# Launch_Tower_Power_Interface_Board_v1-2.net
KiCad netlist of a schematic drawn in EAGLE
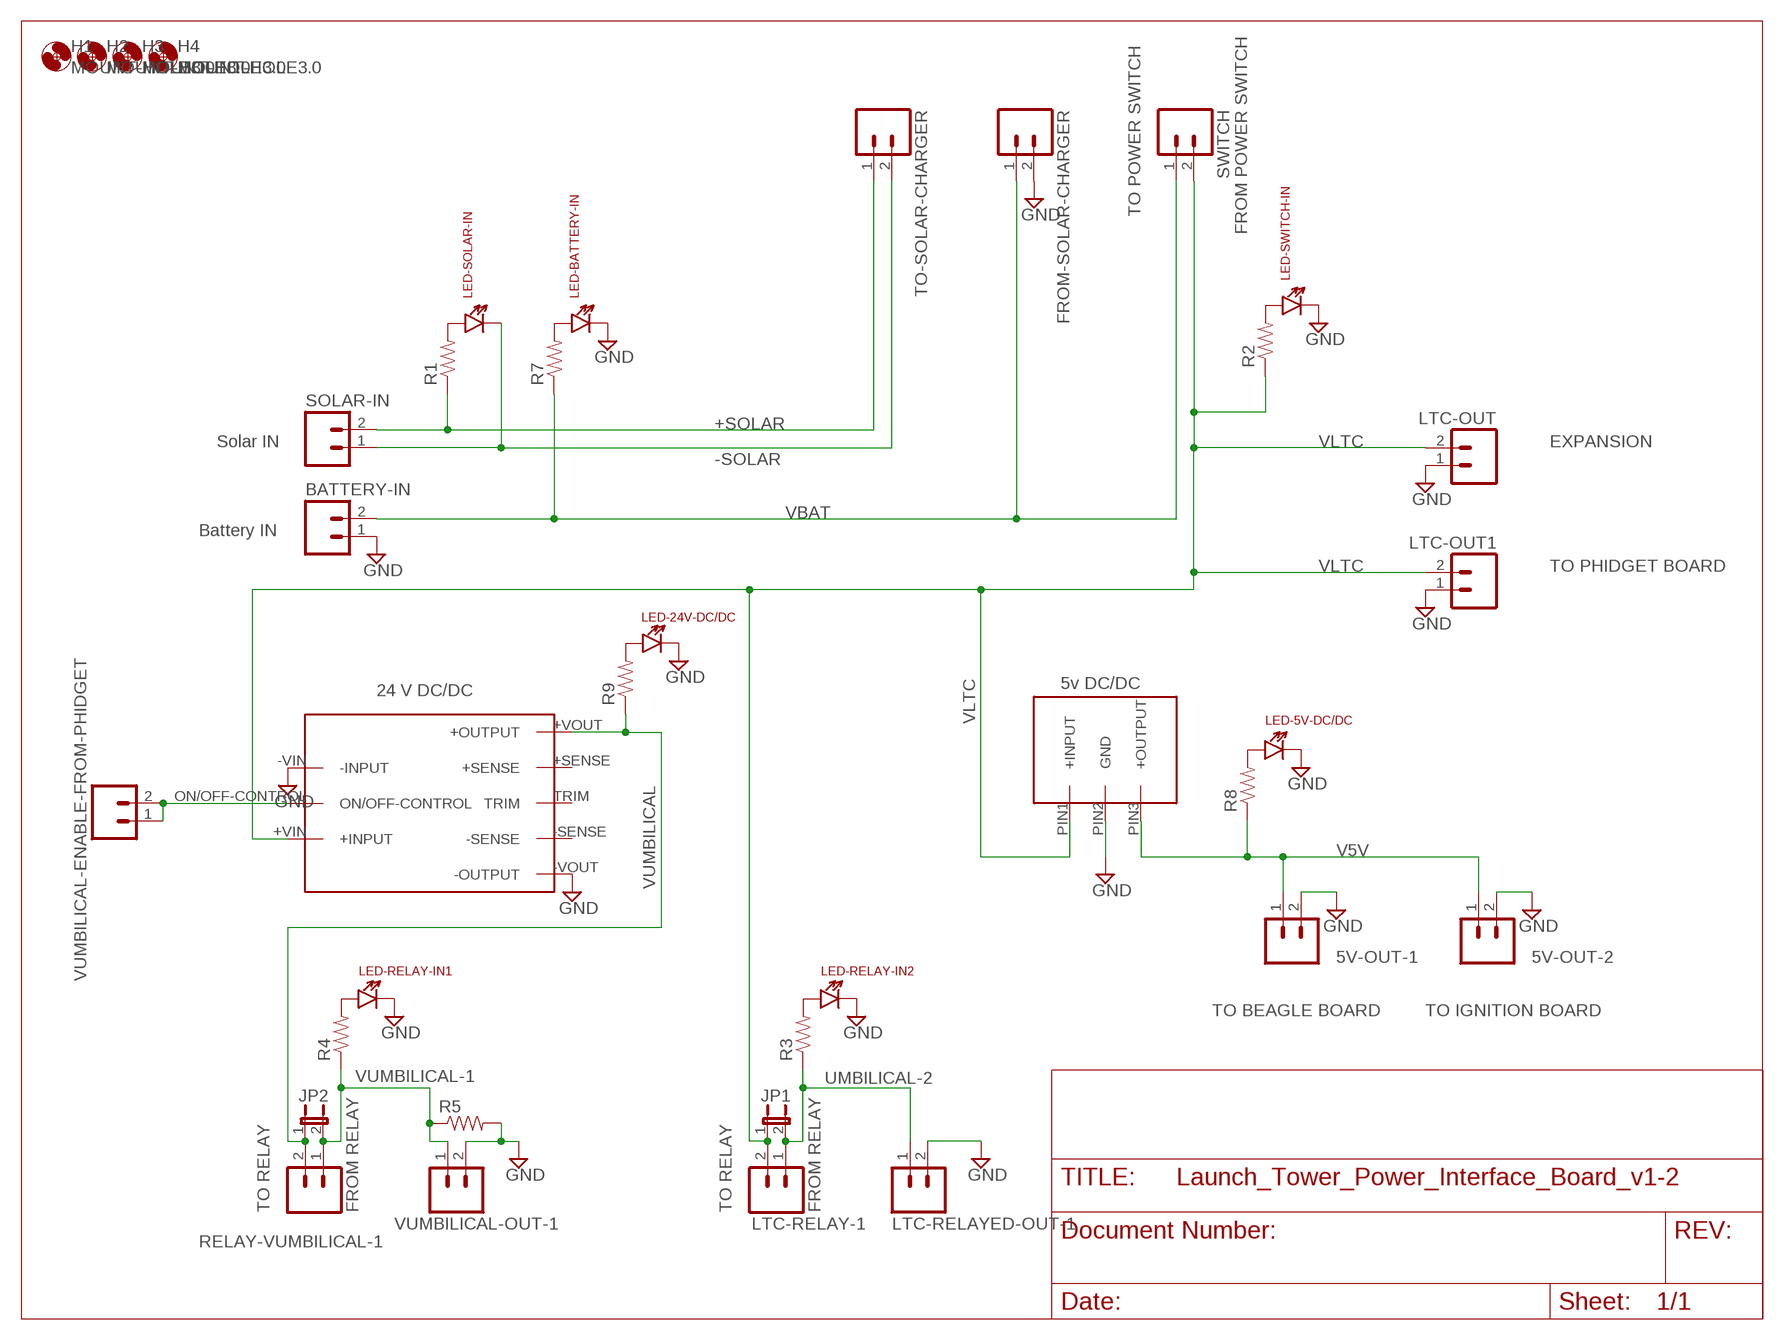
[diagram p0: schematic, sheet 1]

(export (version "E")
  (design (tool "Eeschema 10.0.6"))
  (components
    (comp (ref "5V-OUT-1")
      (value "M025MM")
      (footprint "eagle-import:SCREWTERMINAL-5MM-2")
      (libsource (lib "eagle-import") (part "M025MM"))
    )
    (comp (ref "5V-OUT-2")
      (value "M025MM")
      (footprint "eagle-import:SCREWTERMINAL-5MM-2")
      (libsource (lib "eagle-import") (part "M025MM"))
    )
    (comp (ref "BATTERY-IN")
      (value "M025MM")
      (footprint "eagle-import:SCREWTERMINAL-5MM-2")
      (libsource (lib "eagle-import") (part "M025MM"))
    )
    (comp (ref "FROM-SOLAR-CHARGER")
      (value "M025MM")
      (footprint "eagle-import:SCREWTERMINAL-5MM-2")
      (libsource (lib "eagle-import") (part "M025MM"))
    )
    (comp (ref "H1")
      (value "MOUNT-HOLE3.0")
      (footprint "eagle-import:3,0")
      (libsource (lib "eagle-import") (part "MOUNT-HOLE3.0"))
    )
    (comp (ref "H2")
      (value "MOUNT-HOLE3.0")
      (footprint "eagle-import:3,0")
      (libsource (lib "eagle-import") (part "MOUNT-HOLE3.0"))
    )
    (comp (ref "H3")
      (value "MOUNT-HOLE3.0")
      (footprint "eagle-import:3,0")
      (libsource (lib "eagle-import") (part "MOUNT-HOLE3.0"))
    )
    (comp (ref "H4")
      (value "MOUNT-HOLE3.0")
      (footprint "eagle-import:3,0")
      (libsource (lib "eagle-import") (part "MOUNT-HOLE3.0"))
    )
    (comp (ref "JP1")
      (value "JUMPER-2PTH")
      (footprint "eagle-import:1X02")
      (libsource (lib "eagle-import") (part "JUMPER-2PTH"))
    )
    (comp (ref "JP2")
      (value "JUMPER-2PTH")
      (footprint "eagle-import:1X02")
      (libsource (lib "eagle-import") (part "JUMPER-2PTH"))
    )
    (comp (ref "LED-5V-DC/DC")
      (value "LTE-302")
      (footprint "eagle-import:LTE-302")
      (libsource (lib "eagle-import") (part "LTE-302"))
    )
    (comp (ref "LED-24V-DC/DC")
      (value "LTE-302")
      (footprint "eagle-import:LTE-302")
      (libsource (lib "eagle-import") (part "LTE-302"))
    )
    (comp (ref "LED-BATTERY-IN")
      (value "LTE-302")
      (footprint "eagle-import:LTE-302")
      (libsource (lib "eagle-import") (part "LTE-302"))
    )
    (comp (ref "LED-RELAY-IN1")
      (value "LTE-302")
      (footprint "eagle-import:LTE-302")
      (libsource (lib "eagle-import") (part "LTE-302"))
    )
    (comp (ref "LED-RELAY-IN2")
      (value "LTE-302")
      (footprint "eagle-import:LTE-302")
      (libsource (lib "eagle-import") (part "LTE-302"))
    )
    (comp (ref "LED-SOLAR-IN")
      (value "LTE-302")
      (footprint "eagle-import:LTE-302")
      (libsource (lib "eagle-import") (part "LTE-302"))
    )
    (comp (ref "LED-SWITCH-IN")
      (value "LTE-302")
      (footprint "eagle-import:LTE-302")
      (libsource (lib "eagle-import") (part "LTE-302"))
    )
    (comp (ref "LTC-OUT")
      (value "M025MM")
      (footprint "eagle-import:SCREWTERMINAL-5MM-2")
      (libsource (lib "eagle-import") (part "M025MM"))
    )
    (comp (ref "LTC-OUT1")
      (value "M025MM")
      (footprint "eagle-import:SCREWTERMINAL-5MM-2")
      (libsource (lib "eagle-import") (part "M025MM"))
    )
    (comp (ref "LTC-RELAY-1")
      (value "M025MM")
      (footprint "eagle-import:SCREWTERMINAL-5MM-2")
      (libsource (lib "eagle-import") (part "M025MM"))
    )
    (comp (ref "LTC-RELAYED-OUT-1")
      (value "M025MM")
      (footprint "eagle-import:SCREWTERMINAL-5MM-2")
      (libsource (lib "eagle-import") (part "M025MM"))
    )
    (comp (ref "R1")
      (value "RESISTORPTH-1/2W")
      (footprint "eagle-import:AXIAL-0.5")
      (libsource (lib "eagle-import") (part "RESISTORPTH-1/2W"))
    )
    (comp (ref "R2")
      (value "RESISTORPTH-1/2W")
      (footprint "eagle-import:AXIAL-0.5")
      (libsource (lib "eagle-import") (part "RESISTORPTH-1/2W"))
    )
    (comp (ref "R3")
      (value "RESISTORPTH-1/2W")
      (footprint "eagle-import:AXIAL-0.5")
      (libsource (lib "eagle-import") (part "RESISTORPTH-1/2W"))
    )
    (comp (ref "R4")
      (value "RESISTORPTH-1/2W")
      (footprint "eagle-import:AXIAL-0.5")
      (libsource (lib "eagle-import") (part "RESISTORPTH-1/2W"))
    )
    (comp (ref "R5")
      (value "RESISTORPTH-1/2W")
      (footprint "eagle-import:AXIAL-0.5")
      (libsource (lib "eagle-import") (part "RESISTORPTH-1/2W"))
    )
    (comp (ref "R7")
      (value "RESISTORPTH-1/2W")
      (footprint "eagle-import:AXIAL-0.5")
      (libsource (lib "eagle-import") (part "RESISTORPTH-1/2W"))
    )
    (comp (ref "R8")
      (value "RESISTORPTH-1/2W")
      (footprint "eagle-import:AXIAL-0.5")
      (libsource (lib "eagle-import") (part "RESISTORPTH-1/2W"))
    )
    (comp (ref "R9")
      (value "RESISTORPTH-1/2W")
      (footprint "eagle-import:AXIAL-0.5")
      (libsource (lib "eagle-import") (part "RESISTORPTH-1/2W"))
    )
    (comp (ref "RELAY-VUMBILICAL-1")
      (value "M025MM")
      (footprint "eagle-import:SCREWTERMINAL-5MM-2")
      (libsource (lib "eagle-import") (part "M025MM"))
    )
    (comp (ref "SOLAR-IN")
      (value "M025MM")
      (footprint "eagle-import:SCREWTERMINAL-5MM-2")
      (libsource (lib "eagle-import") (part "M025MM"))
    )
    (comp (ref "SWITCH")
      (value "M025MM")
      (footprint "eagle-import:SCREWTERMINAL-5MM-2")
      (libsource (lib "eagle-import") (part "M025MM"))
    )
    (comp (ref "TO-SOLAR-CHARGER")
      (value "M025MM")
      (footprint "eagle-import:SCREWTERMINAL-5MM-2")
      (libsource (lib "eagle-import") (part "M025MM"))
    )
    (comp (ref "U$1")
      (value "DC/DC_CONV_24V")
      (footprint "eagle-import:UWE")
      (libsource (lib "eagle-import") (part "DC/DC_CONV_24V"))
    )
    (comp (ref "U$2")
      (value "DC/DC_CONV_5V")
      (footprint "eagle-import:OKI-SIP")
      (libsource (lib "eagle-import") (part "DC/DC_CONV_5V"))
    )
    (comp (ref "VUMBILICAL-ENABLE-FROM-PHIDGET")
      (value "M023.5MM")
      (footprint "eagle-import:SCREWTERMINAL-3.5MM-2")
      (libsource (lib "eagle-import") (part "SparkFun-Connectors_M023.5MM"))
    )
    (comp (ref "VUMBILICAL-OUT-1")
      (value "M025MM")
      (footprint "eagle-import:SCREWTERMINAL-5MM-2")
      (libsource (lib "eagle-import") (part "M025MM"))
    )
  )
  (nets
    (net (code "1") (name "/+SOLAR") (class "Default")
      (node (ref "R1") (pin "P$1") (pinfunction "1_P$1") (pintype "passive"))
      (node (ref "SOLAR-IN") (pin "2") (pinfunction "2_2") (pintype "passive"))
      (node (ref "TO-SOLAR-CHARGER") (pin "1") (pinfunction "1_1") (pintype "passive"))
    )
    (net (code "2") (name "/-SOLAR") (class "Default")
      (node (ref "LED-SOLAR-IN") (pin "C") (pinfunction "C_C") (pintype "bidirectional"))
      (node (ref "SOLAR-IN") (pin "1") (pinfunction "1_1") (pintype "passive"))
      (node (ref "TO-SOLAR-CHARGER") (pin "2") (pinfunction "2_2") (pintype "passive"))
    )
    (net (code "3") (name "/UMBILICAL-2") (class "Default")
      (node (ref "JP1") (pin "2") (pinfunction "2_2") (pintype "passive"))
      (node (ref "LTC-RELAY-1") (pin "1") (pinfunction "1_1") (pintype "passive"))
      (node (ref "LTC-RELAYED-OUT-1") (pin "1") (pinfunction "1_1") (pintype "passive"))
      (node (ref "R3") (pin "P$1") (pinfunction "1_P$1") (pintype "passive"))
    )
    (net (code "4") (name "/V5V") (class "Default")
      (node (ref "5V-OUT-1") (pin "1") (pinfunction "1_1") (pintype "passive"))
      (node (ref "5V-OUT-2") (pin "1") (pinfunction "1_1") (pintype "passive"))
      (node (ref "R8") (pin "P$1") (pinfunction "1_P$1") (pintype "passive"))
      (node (ref "U$2") (pin "PIN3") (pinfunction "+OUTPUT_PIN3") (pintype "bidirectional"))
    )
    (net (code "5") (name "/VBAT") (class "Default")
      (node (ref "BATTERY-IN") (pin "2") (pinfunction "2_2") (pintype "passive"))
      (node (ref "FROM-SOLAR-CHARGER") (pin "1") (pinfunction "1_1") (pintype "passive"))
      (node (ref "R7") (pin "P$1") (pinfunction "1_P$1") (pintype "passive"))
      (node (ref "SWITCH") (pin "1") (pinfunction "1_1") (pintype "passive"))
    )
    (net (code "6") (name "/VLTC") (class "Default")
      (node (ref "JP1") (pin "1") (pinfunction "1_1") (pintype "passive"))
      (node (ref "LTC-OUT") (pin "2") (pinfunction "2_2") (pintype "passive"))
      (node (ref "LTC-OUT1") (pin "2") (pinfunction "2_2") (pintype "passive"))
      (node (ref "LTC-RELAY-1") (pin "2") (pinfunction "2_2") (pintype "passive"))
      (node (ref "R2") (pin "P$1") (pinfunction "1_P$1") (pintype "passive"))
      (node (ref "SWITCH") (pin "2") (pinfunction "2_2") (pintype "passive"))
      (node (ref "U$1") (pin "+VIN") (pinfunction "+INPUT_+VIN") (pintype "bidirectional"))
      (node (ref "U$2") (pin "PIN1") (pinfunction "+INPUT_PIN1") (pintype "bidirectional"))
    )
    (net (code "7") (name "/VUMBILICAL") (class "Default")
      (node (ref "JP2") (pin "1") (pinfunction "1_1") (pintype "passive"))
      (node (ref "R9") (pin "P$1") (pinfunction "1_P$1") (pintype "passive"))
      (node (ref "RELAY-VUMBILICAL-1") (pin "2") (pinfunction "2_2") (pintype "passive"))
      (node (ref "U$1") (pin "+VOUT") (pinfunction "+OUTPUT_+VOUT") (pintype "bidirectional"))
    )
    (net (code "8") (name "/VUMBILICAL-1") (class "Default")
      (node (ref "JP2") (pin "2") (pinfunction "2_2") (pintype "passive"))
      (node (ref "R4") (pin "P$1") (pinfunction "1_P$1") (pintype "passive"))
      (node (ref "R5") (pin "P$1") (pinfunction "1_P$1") (pintype "passive"))
      (node (ref "RELAY-VUMBILICAL-1") (pin "1") (pinfunction "1_1") (pintype "passive"))
      (node (ref "VUMBILICAL-OUT-1") (pin "1") (pinfunction "1_1") (pintype "passive"))
    )
    (net (code "9") (name "GND") (class "Default")
      (node (ref "5V-OUT-1") (pin "2") (pinfunction "2_2") (pintype "passive"))
      (node (ref "5V-OUT-2") (pin "2") (pinfunction "2_2") (pintype "passive"))
      (node (ref "BATTERY-IN") (pin "1") (pinfunction "1_1") (pintype "passive"))
      (node (ref "FROM-SOLAR-CHARGER") (pin "2") (pinfunction "2_2") (pintype "passive"))
      (node (ref "LED-24V-DC/DC") (pin "C") (pinfunction "C_C") (pintype "bidirectional"))
      (node (ref "LED-5V-DC/DC") (pin "C") (pinfunction "C_C") (pintype "bidirectional"))
      (node (ref "LED-BATTERY-IN") (pin "C") (pinfunction "C_C") (pintype "bidirectional"))
      (node (ref "LED-RELAY-IN1") (pin "C") (pinfunction "C_C") (pintype "bidirectional"))
      (node (ref "LED-RELAY-IN2") (pin "C") (pinfunction "C_C") (pintype "bidirectional"))
      (node (ref "LED-SWITCH-IN") (pin "C") (pinfunction "C_C") (pintype "bidirectional"))
      (node (ref "LTC-OUT") (pin "1") (pinfunction "1_1") (pintype "passive"))
      (node (ref "LTC-OUT1") (pin "1") (pinfunction "1_1") (pintype "passive"))
      (node (ref "LTC-RELAYED-OUT-1") (pin "2") (pinfunction "2_2") (pintype "passive"))
      (node (ref "R5") (pin "P$2") (pinfunction "2_P$2") (pintype "passive"))
      (node (ref "U$1") (pin "-VIN") (pinfunction "-INPUT_-VIN") (pintype "bidirectional"))
      (node (ref "U$1") (pin "-VOUT") (pinfunction "-OUTPUT_-VOUT") (pintype "bidirectional"))
      (node (ref "U$2") (pin "PIN2") (pinfunction "GND_PIN2") (pintype "bidirectional"))
      (node (ref "VUMBILICAL-OUT-1") (pin "2") (pinfunction "2_2") (pintype "passive"))
    )
    (net (code "10") (name "Net-(R1-2)") (class "Default")
      (node (ref "LED-SOLAR-IN") (pin "A") (pinfunction "A_A") (pintype "bidirectional"))
      (node (ref "R1") (pin "P$2") (pinfunction "2_P$2") (pintype "passive"))
    )
    (net (code "11") (name "Net-(R2-2)") (class "Default")
      (node (ref "LED-SWITCH-IN") (pin "A") (pinfunction "A_A") (pintype "bidirectional"))
      (node (ref "R2") (pin "P$2") (pinfunction "2_P$2") (pintype "passive"))
    )
    (net (code "12") (name "Net-(R3-2)") (class "Default")
      (node (ref "LED-RELAY-IN2") (pin "A") (pinfunction "A_A") (pintype "bidirectional"))
      (node (ref "R3") (pin "P$2") (pinfunction "2_P$2") (pintype "passive"))
    )
    (net (code "13") (name "Net-(R4-2)") (class "Default")
      (node (ref "LED-RELAY-IN1") (pin "A") (pinfunction "A_A") (pintype "bidirectional"))
      (node (ref "R4") (pin "P$2") (pinfunction "2_P$2") (pintype "passive"))
    )
    (net (code "14") (name "Net-(R7-2)") (class "Default")
      (node (ref "LED-BATTERY-IN") (pin "A") (pinfunction "A_A") (pintype "bidirectional"))
      (node (ref "R7") (pin "P$2") (pinfunction "2_P$2") (pintype "passive"))
    )
    (net (code "15") (name "Net-(R8-2)") (class "Default")
      (node (ref "LED-5V-DC/DC") (pin "A") (pinfunction "A_A") (pintype "bidirectional"))
      (node (ref "R8") (pin "P$2") (pinfunction "2_P$2") (pintype "passive"))
    )
    (net (code "16") (name "Net-(R9-2)") (class "Default")
      (node (ref "LED-24V-DC/DC") (pin "A") (pinfunction "A_A") (pintype "bidirectional"))
      (node (ref "R9") (pin "P$2") (pinfunction "2_P$2") (pintype "passive"))
    )
    (net (code "17") (name "Net-(U$1-PadON{slash}OFF-CONTROL)") (class "Default")
      (node (ref "U$1") (pin "ON/OFF-CONTROL") (pinfunction "ON/OFF-CONTROL_ON/OFF-CONTROL") (pintype "bidirectional"))
      (node (ref "VUMBILICAL-ENABLE-FROM-PHIDGET") (pin "1") (pinfunction "1_1") (pintype "passive"))
      (node (ref "VUMBILICAL-ENABLE-FROM-PHIDGET") (pin "2") (pinfunction "2_2") (pintype "passive"))
    )
    (net (code "18") (name "unconnected-(U$1-Pad+SENSE)") (class "Default")
      (node (ref "U$1") (pin "+SENSE") (pinfunction "+SENSE_+SENSE") (pintype "bidirectional"))
    )
    (net (code "19") (name "unconnected-(U$1-Pad-SENSE)") (class "Default")
      (node (ref "U$1") (pin "-SENSE") (pinfunction "-SENSE_-SENSE") (pintype "bidirectional"))
    )
    (net (code "20") (name "unconnected-(U$1-PadTRIM)") (class "Default")
      (node (ref "U$1") (pin "TRIM") (pinfunction "TRIM_TRIM") (pintype "bidirectional"))
    )
  )
)
